# Clock2_2.net
KiCad netlist of a schematic drawn in EAGLE
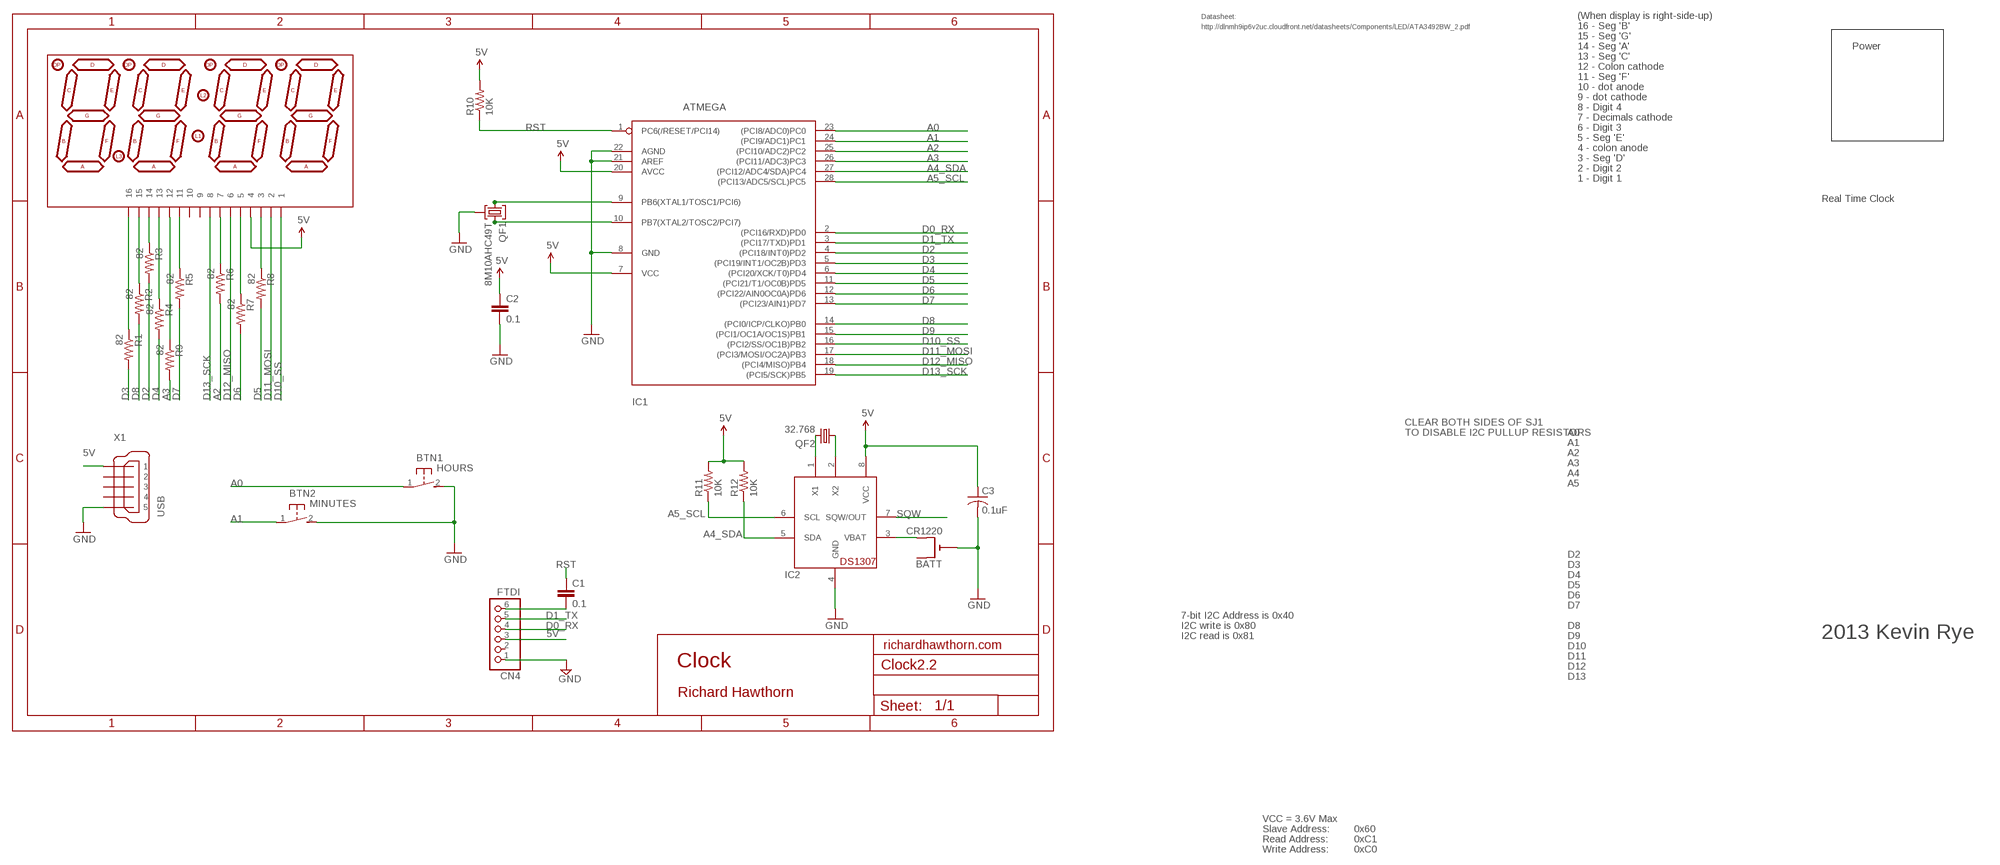
[diagram p0: schematic, sheet 1]

(export (version "E")
  (design (tool "Eeschema 10.0.6"))
  (components
    (comp (ref "BATT")
      (value "CR1220")
      (footprint "eagle-import:CR1220-SMD")
      (libsource (lib "eagle-import") (part "CR1220SMT"))
    )
    (comp (ref "BTN1")
      (value "HOURS")
      (footprint "eagle-import:DTS-3")
      (libsource (lib "eagle-import") (part "DTS-3"))
    )
    (comp (ref "BTN2")
      (value "MINUTES")
      (footprint "eagle-import:DTS-3")
      (libsource (lib "eagle-import") (part "DTS-3"))
    )
    (comp (ref "C1")
      (value "0.1")
      (footprint "eagle-import:CAP-PTH-SMALL2")
      (libsource (lib "eagle-import") (part "CAPPTH2"))
    )
    (comp (ref "C2")
      (value "0.1")
      (footprint "eagle-import:CAP-PTH-SMALL2")
      (libsource (lib "eagle-import") (part "CAPPTH2"))
    )
    (comp (ref "C3")
      (value "0.1uF")
      (footprint "eagle-import:C025-025X050")
      (libsource (lib "eagle-import") (part "C-US025-025X050"))
    )
    (comp (ref "CN4")
      (value "FTDI")
      (footprint "eagle-import:1X06")
      (libsource (lib "eagle-import") (part "PINHD-1X6"))
    )
    (comp (ref "IC1")
      (value "ATMEGA")
      (footprint "eagle-import:DIL28-3-ROUND")
      (libsource (lib "eagle-import") (part "ATMEGA168PROUND"))
    )
    (comp (ref "IC2")
      (value "DS1307")
      (footprint "eagle-import:DIL08")
      (libsource (lib "eagle-import") (part "DS1307"))
    )
    (comp (ref "LED1")
      (value "7SEG-4DIGIT")
      (footprint "eagle-import:SPARKFUN_7-SEGMENT-4DIGIT")
      (libsource (lib "eagle-import") (part "7SEG-4DIGIT"))
    )
    (comp (ref "QF1")
      (value "8M10AHC49T")
      (footprint "eagle-import:HC49U")
      (libsource (lib "eagle-import") (part "8M10AHC49T"))
    )
    (comp (ref "QF2")
      (value "32.768")
      (footprint "eagle-import:TC38H")
      (libsource (lib "eagle-import") (part "CRYTALTC38H"))
    )
    (comp (ref "R1")
      (value "82")
      (footprint "eagle-import:0204_7")
      (libsource (lib "eagle-import") (part "R-US_0204/7"))
    )
    (comp (ref "R2")
      (value "82")
      (footprint "eagle-import:0204_7")
      (libsource (lib "eagle-import") (part "R-US_0204/7"))
    )
    (comp (ref "R3")
      (value "82")
      (footprint "eagle-import:0204_7")
      (libsource (lib "eagle-import") (part "R-US_0204/7"))
    )
    (comp (ref "R4")
      (value "82")
      (footprint "eagle-import:0204_7")
      (libsource (lib "eagle-import") (part "R-US_0204/7"))
    )
    (comp (ref "R5")
      (value "82")
      (footprint "eagle-import:0204_7")
      (libsource (lib "eagle-import") (part "R-US_0204/7"))
    )
    (comp (ref "R6")
      (value "82")
      (footprint "eagle-import:0204_7")
      (libsource (lib "eagle-import") (part "R-US_0204/7"))
    )
    (comp (ref "R7")
      (value "82")
      (footprint "eagle-import:0204_7")
      (libsource (lib "eagle-import") (part "R-US_0204/7"))
    )
    (comp (ref "R8")
      (value "82")
      (footprint "eagle-import:0204_7")
      (libsource (lib "eagle-import") (part "R-US_0204/7"))
    )
    (comp (ref "R9")
      (value "82")
      (footprint "eagle-import:0204_7")
      (libsource (lib "eagle-import") (part "R-US_0204/7"))
    )
    (comp (ref "R10")
      (value "10K")
      (footprint "eagle-import:0204_7")
      (libsource (lib "eagle-import") (part "R-US_0204/7"))
    )
    (comp (ref "R11")
      (value "10K")
      (footprint "eagle-import:0204_7")
      (libsource (lib "eagle-import") (part "R-US_0204/7"))
    )
    (comp (ref "R12")
      (value "10K")
      (footprint "eagle-import:0204_7")
      (libsource (lib "eagle-import") (part "R-US_0204/7"))
    )
    (comp (ref "X1")
      (value "USB")
      (footprint "eagle-import:32005-601")
      (libsource (lib "eagle-import") (part "MINI-USB_SHIELD5P2-32005-601"))
    )
  )
  (nets
    (net (code "1") (name "/A0") (class "Default")
      (node (ref "BTN1") (pin "1") (pinfunction "1_1") (pintype "passive"))
      (node (ref "IC1") (pin "23") (pinfunction "(PCI8/ADC0)PC0_23") (pintype "bidirectional"))
    )
    (net (code "2") (name "/A1") (class "Default")
      (node (ref "BTN2") (pin "1") (pinfunction "1_1") (pintype "passive"))
      (node (ref "IC1") (pin "24") (pinfunction "(PCI9/ADC1)PC1_24") (pintype "bidirectional"))
    )
    (net (code "3") (name "/A2") (class "Default")
      (node (ref "IC1") (pin "25") (pinfunction "(PCI10/ADC2)PC2_25") (pintype "bidirectional"))
      (node (ref "R6") (pin "2") (pinfunction "2_2") (pintype "passive"))
    )
    (net (code "4") (name "/A3") (class "Default")
      (node (ref "IC1") (pin "26") (pinfunction "(PCI11/ADC3)PC3_26") (pintype "bidirectional"))
      (node (ref "R9") (pin "2") (pinfunction "2_2") (pintype "passive"))
    )
    (net (code "5") (name "/A4_SDA") (class "Default")
      (node (ref "IC1") (pin "27") (pinfunction "(PCI12/ADC4/SDA)PC4_27") (pintype "bidirectional"))
      (node (ref "IC2") (pin "5") (pinfunction "SDA_5") (pintype "bidirectional"))
      (node (ref "R12") (pin "1") (pinfunction "1_1") (pintype "passive"))
    )
    (net (code "6") (name "/A5_SCL") (class "Default")
      (node (ref "IC1") (pin "28") (pinfunction "(PCI13/ADC5/SCL)PC5_28") (pintype "bidirectional"))
      (node (ref "IC2") (pin "6") (pinfunction "SCL_6") (pintype "bidirectional"))
      (node (ref "R11") (pin "1") (pinfunction "1_1") (pintype "passive"))
    )
    (net (code "7") (name "/D0_RX") (class "Default")
      (node (ref "CN4") (pin "4") (pinfunction "4_4") (pintype "passive"))
      (node (ref "IC1") (pin "2") (pinfunction "(PCI16/RXD)PD0_2") (pintype "bidirectional"))
    )
    (net (code "8") (name "/D1_TX") (class "Default")
      (node (ref "CN4") (pin "5") (pinfunction "5_5") (pintype "passive"))
      (node (ref "IC1") (pin "3") (pinfunction "(PCI17/TXD)PD1_3") (pintype "bidirectional"))
    )
    (net (code "9") (name "/D2") (class "Default")
      (node (ref "IC1") (pin "4") (pinfunction "(PCI18/INT0)PD2_4") (pintype "bidirectional"))
      (node (ref "R3") (pin "2") (pinfunction "2_2") (pintype "passive"))
    )
    (net (code "10") (name "/D3") (class "Default")
      (node (ref "IC1") (pin "5") (pinfunction "(PCI19/INT1/OC2B)PD3_5") (pintype "bidirectional"))
      (node (ref "R1") (pin "2") (pinfunction "2_2") (pintype "passive"))
    )
    (net (code "11") (name "/D4") (class "Default")
      (node (ref "IC1") (pin "6") (pinfunction "(PCI20/XCK/T0)PD4_6") (pintype "bidirectional"))
      (node (ref "R4") (pin "2") (pinfunction "2_2") (pintype "passive"))
    )
    (net (code "12") (name "/D5") (class "Default")
      (node (ref "IC1") (pin "11") (pinfunction "(PCI21/T1/OC0B)PD5_11") (pintype "bidirectional"))
      (node (ref "R8") (pin "2") (pinfunction "2_2") (pintype "passive"))
    )
    (net (code "13") (name "/D6") (class "Default")
      (node (ref "IC1") (pin "12") (pinfunction "(PCI22/AIN0OC0A)PD6_12") (pintype "bidirectional"))
      (node (ref "R7") (pin "2") (pinfunction "2_2") (pintype "passive"))
    )
    (net (code "14") (name "/D7") (class "Default")
      (node (ref "IC1") (pin "13") (pinfunction "(PCI23/AIN1)PD7_13") (pintype "bidirectional"))
      (node (ref "R5") (pin "2") (pinfunction "2_2") (pintype "passive"))
    )
    (net (code "15") (name "/D8") (class "Default")
      (node (ref "IC1") (pin "14") (pinfunction "(PCI0/ICP/CLKO)PB0_14") (pintype "bidirectional"))
      (node (ref "R2") (pin "2") (pinfunction "2_2") (pintype "passive"))
    )
    (net (code "16") (name "/D9") (class "Default")
      (node (ref "IC1") (pin "15") (pinfunction "(PCI1/OC1A/OC1S)PB1_15") (pintype "bidirectional"))
    )
    (net (code "17") (name "/D10_SS") (class "Default")
      (node (ref "IC1") (pin "16") (pinfunction "(PCI2/SS/OC1B)PB2_16") (pintype "bidirectional"))
      (node (ref "LED1") (pin "1") (pinfunction "1_1") (pintype "bidirectional"))
    )
    (net (code "18") (name "/D11_MOSI") (class "Default")
      (node (ref "IC1") (pin "17") (pinfunction "(PCI3/MOSI/OC2A)PB3_17") (pintype "bidirectional"))
      (node (ref "LED1") (pin "2") (pinfunction "2_2") (pintype "bidirectional"))
    )
    (net (code "19") (name "/D12_MISO") (class "Default")
      (node (ref "IC1") (pin "18") (pinfunction "(PCI4/MISO)PB4_18") (pintype "bidirectional"))
      (node (ref "LED1") (pin "6") (pinfunction "6_6") (pintype "bidirectional"))
    )
    (net (code "20") (name "/D13_SCK") (class "Default")
      (node (ref "IC1") (pin "19") (pinfunction "(PCI5/SCK)PB5_19") (pintype "bidirectional"))
      (node (ref "LED1") (pin "8") (pinfunction "8_8") (pintype "bidirectional"))
    )
    (net (code "21") (name "/RST") (class "Default")
      (node (ref "C1") (pin "1") (pinfunction "1_1") (pintype "passive"))
      (node (ref "IC1") (pin "1") (pinfunction "PC6(/RESET/PCI14)_1") (pintype "bidirectional"))
      (node (ref "R10") (pin "1") (pinfunction "1_1") (pintype "passive"))
    )
    (net (code "22") (name "/SQW") (class "Default")
      (node (ref "IC2") (pin "7") (pinfunction "SQW/OUT_7") (pintype "bidirectional"))
    )
    (net (code "23") (name "5V") (class "Default")
      (node (ref "C2") (pin "1") (pinfunction "1_1") (pintype "passive"))
      (node (ref "C3") (pin "1") (pinfunction "1_1") (pintype "passive"))
      (node (ref "CN4") (pin "3") (pinfunction "3_3") (pintype "passive"))
      (node (ref "IC1") (pin "20") (pinfunction "AVCC_20") (pintype "bidirectional"))
      (node (ref "IC1") (pin "7") (pinfunction "VCC_7") (pintype "bidirectional"))
      (node (ref "IC2") (pin "8") (pinfunction "VCC_8") (pintype "power_in"))
      (node (ref "LED1") (pin "4") (pinfunction "4_4") (pintype "bidirectional"))
      (node (ref "R10") (pin "2") (pinfunction "2_2") (pintype "passive"))
      (node (ref "R11") (pin "2") (pinfunction "2_2") (pintype "passive"))
      (node (ref "R12") (pin "2") (pinfunction "2_2") (pintype "passive"))
      (node (ref "X1") (pin "1") (pinfunction "1_1") (pintype "passive"))
    )
    (net (code "24") (name "GND") (class "Default")
      (node (ref "BATT") (pin "-") (pinfunction "-_-") (pintype "passive"))
      (node (ref "BTN1") (pin "2") (pinfunction "2_2") (pintype "passive"))
      (node (ref "BTN2") (pin "2") (pinfunction "2_2") (pintype "passive"))
      (node (ref "C2") (pin "2") (pinfunction "2_2") (pintype "passive"))
      (node (ref "C3") (pin "2") (pinfunction "2_2") (pintype "passive"))
      (node (ref "CN4") (pin "1") (pinfunction "1_1") (pintype "passive"))
      (node (ref "IC1") (pin "21") (pinfunction "AREF_21") (pintype "bidirectional"))
      (node (ref "IC1") (pin "22") (pinfunction "AGND_22") (pintype "bidirectional"))
      (node (ref "IC1") (pin "8") (pinfunction "GND_8") (pintype "bidirectional"))
      (node (ref "IC2") (pin "4") (pinfunction "GND_4") (pintype "power_in"))
      (node (ref "QF1") (pin "2") (pinfunction "2_2") (pintype "passive"))
      (node (ref "X1") (pin "5") (pinfunction "5_5") (pintype "passive"))
    )
    (net (code "25") (name "Net-(BATT-+1)") (class "Default")
      (node (ref "BATT") (pin "+$2") (pinfunction "+1_+$2") (pintype "passive"))
      (node (ref "IC2") (pin "3") (pinfunction "VBAT_3") (pintype "power_in"))
    )
    (net (code "26") (name "Net-(C1-Pad2)") (class "Default")
      (node (ref "C1") (pin "2") (pinfunction "2_2") (pintype "passive"))
      (node (ref "CN4") (pin "6") (pinfunction "6_6") (pintype "passive"))
    )
    (net (code "27") (name "Net-(IC1-PB6(XTAL1{slash}TOSC1{slash}PCI6))") (class "Default")
      (node (ref "IC1") (pin "9") (pinfunction "PB6(XTAL1/TOSC1/PCI6)_9") (pintype "bidirectional"))
      (node (ref "QF1") (pin "1") (pinfunction "1_1") (pintype "passive"))
    )
    (net (code "28") (name "Net-(IC1-PB7(XTAL2{slash}TOSC2{slash}PCI7))") (class "Default")
      (node (ref "IC1") (pin "10") (pinfunction "PB7(XTAL2/TOSC2/PCI7)_10") (pintype "bidirectional"))
      (node (ref "QF1") (pin "3") (pinfunction "3_3") (pintype "passive"))
    )
    (net (code "29") (name "Net-(IC2-X1)") (class "Default")
      (node (ref "IC2") (pin "1") (pinfunction "X1_1") (pintype "passive"))
      (node (ref "QF2") (pin "2") (pinfunction "2_2") (pintype "passive"))
    )
    (net (code "30") (name "Net-(IC2-X2)") (class "Default")
      (node (ref "IC2") (pin "2") (pinfunction "X2_2") (pintype "passive"))
      (node (ref "QF2") (pin "1") (pinfunction "1_1") (pintype "passive"))
    )
    (net (code "31") (name "Net-(LED1-Pad3)") (class "Default")
      (node (ref "LED1") (pin "3") (pinfunction "3_3") (pintype "bidirectional"))
      (node (ref "R8") (pin "1") (pinfunction "1_1") (pintype "passive"))
    )
    (net (code "32") (name "Net-(LED1-Pad5)") (class "Default")
      (node (ref "LED1") (pin "5") (pinfunction "5_5") (pintype "bidirectional"))
      (node (ref "R7") (pin "1") (pinfunction "1_1") (pintype "passive"))
    )
    (net (code "33") (name "Net-(LED1-Pad7)") (class "Default")
      (node (ref "LED1") (pin "7") (pinfunction "7_7") (pintype "bidirectional"))
      (node (ref "R6") (pin "1") (pinfunction "1_1") (pintype "passive"))
    )
    (net (code "34") (name "Net-(LED1-Pad11)") (class "Default")
      (node (ref "LED1") (pin "11") (pinfunction "11_11") (pintype "bidirectional"))
      (node (ref "R5") (pin "1") (pinfunction "1_1") (pintype "passive"))
    )
    (net (code "35") (name "Net-(LED1-Pad12)") (class "Default")
      (node (ref "LED1") (pin "12") (pinfunction "12_12") (pintype "bidirectional"))
      (node (ref "R9") (pin "1") (pinfunction "1_1") (pintype "passive"))
    )
    (net (code "36") (name "Net-(LED1-Pad13)") (class "Default")
      (node (ref "LED1") (pin "13") (pinfunction "13_13") (pintype "bidirectional"))
      (node (ref "R4") (pin "1") (pinfunction "1_1") (pintype "passive"))
    )
    (net (code "37") (name "Net-(LED1-Pad14)") (class "Default")
      (node (ref "LED1") (pin "14") (pinfunction "14_14") (pintype "bidirectional"))
      (node (ref "R3") (pin "1") (pinfunction "1_1") (pintype "passive"))
    )
    (net (code "38") (name "Net-(LED1-Pad15)") (class "Default")
      (node (ref "LED1") (pin "15") (pinfunction "15_15") (pintype "bidirectional"))
      (node (ref "R2") (pin "1") (pinfunction "1_1") (pintype "passive"))
    )
    (net (code "39") (name "Net-(LED1-Pad16)") (class "Default")
      (node (ref "LED1") (pin "16") (pinfunction "16_16") (pintype "bidirectional"))
      (node (ref "R1") (pin "1") (pinfunction "1_1") (pintype "passive"))
    )
    (net (code "40") (name "unconnected-(BATT-+-Pad+$1)") (class "Default")
      (node (ref "BATT") (pin "+$1") (pinfunction "+_+$1") (pintype "passive"))
    )
    (net (code "41") (name "unconnected-(CN4-Pad2)") (class "Default")
      (node (ref "CN4") (pin "2") (pinfunction "2_2") (pintype "passive"))
    )
    (net (code "42") (name "unconnected-(LED1-Pad9)") (class "Default")
      (node (ref "LED1") (pin "9") (pinfunction "9_9") (pintype "bidirectional"))
    )
    (net (code "43") (name "unconnected-(LED1-Pad10)") (class "Default")
      (node (ref "LED1") (pin "10") (pinfunction "10_10") (pintype "bidirectional"))
    )
    (net (code "44") (name "unconnected-(X1-Pad2)") (class "Default")
      (node (ref "X1") (pin "2") (pinfunction "2_2") (pintype "passive"))
    )
    (net (code "45") (name "unconnected-(X1-Pad3)") (class "Default")
      (node (ref "X1") (pin "3") (pinfunction "3_3") (pintype "passive"))
    )
    (net (code "46") (name "unconnected-(X1-Pad4)") (class "Default")
      (node (ref "X1") (pin "4") (pinfunction "4_4") (pintype "passive"))
    )
  )
)
